# TempSensor.net
KiCad netlist of a schematic drawn in Altium Designer
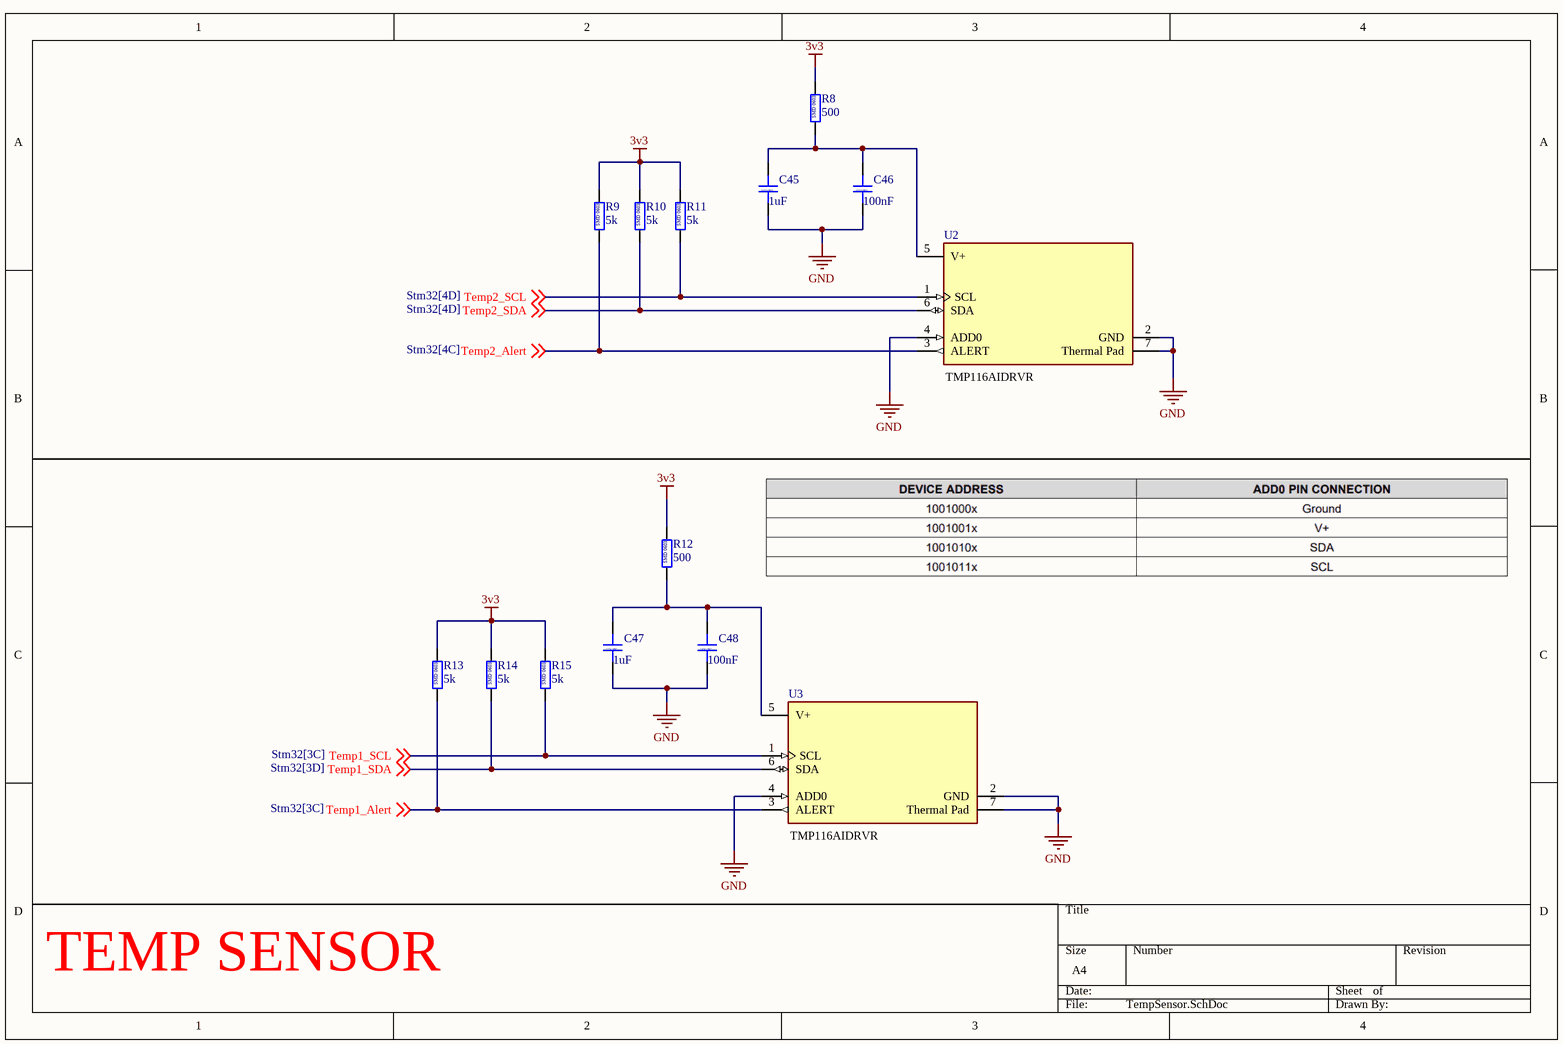
[diagram p0: TempSensor.SchDoc]

(export (version "E")
  (design (tool "Eeschema 10.0.6"))
  (components
    (comp (ref "C45")
      (value "1uF")
      (footprint "CAP_0603")
      (description "Capacitor SMD 0603 RATED")
      (libsource (lib "STeRG-Passives-Standard") (part "Capacitor-SMD-0603"))
    )
    (comp (ref "C46")
      (value "100nF")
      (footprint "CAP_0603")
      (description "Capacitor SMD 0603 RATED")
      (libsource (lib "STeRG-Passives-Standard") (part "Capacitor-SMD-0603"))
    )
    (comp (ref "C47")
      (value "1uF")
      (footprint "CAP_0603")
      (description "Capacitor SMD 0603 RATED")
      (libsource (lib "STeRG-Passives-Standard") (part "Capacitor-SMD-0603"))
    )
    (comp (ref "C48")
      (value "100nF")
      (footprint "CAP_0603")
      (description "Capacitor SMD 0603 RATED")
      (libsource (lib "STeRG-Passives-Standard") (part "Capacitor-SMD-0603"))
    )
    (comp (ref "R8")
      (value "500")
      (footprint "RES_0603")
      (description "Resistor SMD 0603 RATED")
      (libsource (lib "STeRG-Passives-Standard") (part "Resistor-SMD-0603"))
    )
    (comp (ref "R9")
      (value "5k")
      (footprint "RES_0603")
      (description "Resistor SMD 0603 RATED")
      (libsource (lib "STeRG-Passives-Standard") (part "Resistor-SMD-0603"))
    )
    (comp (ref "R10")
      (value "5k")
      (footprint "RES_0603")
      (description "Resistor SMD 0603 RATED")
      (libsource (lib "STeRG-Passives-Standard") (part "Resistor-SMD-0603"))
    )
    (comp (ref "R11")
      (value "5k")
      (footprint "RES_0603")
      (description "Resistor SMD 0603 RATED")
      (libsource (lib "STeRG-Passives-Standard") (part "Resistor-SMD-0603"))
    )
    (comp (ref "R12")
      (value "500")
      (footprint "RES_0603")
      (description "Resistor SMD 0603 RATED")
      (libsource (lib "STeRG-Passives-Standard") (part "Resistor-SMD-0603"))
    )
    (comp (ref "R13")
      (value "5k")
      (footprint "RES_0603")
      (description "Resistor SMD 0603 RATED")
      (libsource (lib "STeRG-Passives-Standard") (part "Resistor-SMD-0603"))
    )
    (comp (ref "R14")
      (value "5k")
      (footprint "RES_0603")
      (description "Resistor SMD 0603 RATED")
      (libsource (lib "STeRG-Passives-Standard") (part "Resistor-SMD-0603"))
    )
    (comp (ref "R15")
      (value "5k")
      (footprint "RES_0603")
      (description "Resistor SMD 0603 RATED")
      (libsource (lib "STeRG-Passives-Standard") (part "Resistor-SMD-0603"))
    )
    (comp (ref "U2")
      (value "~")
      (footprint "FP-DRV0006A-IPC_C")
      (description "SENSOR DIGITAL -55C-125C 6WSON")
      (libsource (lib "Altium Content Vault") (part "a617691ba8d4fd78c31dab07a1f4092"))
    )
    (comp (ref "U3")
      (value "~")
      (footprint "FP-DRV0006A-IPC_C")
      (description "SENSOR DIGITAL -55C-125C 6WSON")
      (libsource (lib "Altium Content Vault") (part "a617691ba8d4fd78c31dab07a1f4092"))
    )
  )
  (nets
    (net (code "1") (name "3v3") (class "Default")
      (node (ref "R10") (pin "2") (pinfunction "2_2") (pintype "passive"))
      (node (ref "R11") (pin "2") (pinfunction "2_2") (pintype "passive"))
      (node (ref "R12") (pin "2") (pinfunction "2_2") (pintype "passive"))
      (node (ref "R13") (pin "2") (pinfunction "2_2") (pintype "passive"))
      (node (ref "R14") (pin "2") (pinfunction "2_2") (pintype "passive"))
      (node (ref "R15") (pin "2") (pinfunction "2_2") (pintype "passive"))
      (node (ref "R8") (pin "2") (pinfunction "2_2") (pintype "passive"))
      (node (ref "R9") (pin "2") (pinfunction "2_2") (pintype "passive"))
    )
    (net (code "2") (name "GND") (class "Default")
      (node (ref "C45") (pin "1") (pinfunction "1_1") (pintype "passive"))
      (node (ref "C46") (pin "1") (pinfunction "1_1") (pintype "passive"))
      (node (ref "C47") (pin "1") (pinfunction "1_1") (pintype "passive"))
      (node (ref "C48") (pin "1") (pinfunction "1_1") (pintype "passive"))
      (node (ref "U2") (pin "2") (pinfunction "GND_2") (pintype "power_in"))
      (node (ref "U2") (pin "4") (pinfunction "ADD0_4") (pintype "input"))
      (node (ref "U2") (pin "7") (pinfunction "Thermal_Pad_7") (pintype "passive"))
      (node (ref "U3") (pin "2") (pinfunction "GND_2") (pintype "power_in"))
      (node (ref "U3") (pin "4") (pinfunction "ADD0_4") (pintype "input"))
      (node (ref "U3") (pin "7") (pinfunction "Thermal_Pad_7") (pintype "passive"))
    )
    (net (code "3") (name "Net-(U2-V+)") (class "Default")
      (node (ref "C45") (pin "2") (pinfunction "2_2") (pintype "passive"))
      (node (ref "C46") (pin "2") (pinfunction "2_2") (pintype "passive"))
      (node (ref "R8") (pin "1") (pinfunction "1_1") (pintype "passive"))
      (node (ref "U2") (pin "5") (pinfunction "V+_5") (pintype "power_in"))
    )
    (net (code "4") (name "Net-(U3-V+)") (class "Default")
      (node (ref "C47") (pin "2") (pinfunction "2_2") (pintype "passive"))
      (node (ref "C48") (pin "2") (pinfunction "2_2") (pintype "passive"))
      (node (ref "R12") (pin "1") (pinfunction "1_1") (pintype "passive"))
      (node (ref "U3") (pin "5") (pinfunction "V+_5") (pintype "power_in"))
    )
    (net (code "5") (name "Temp1_Alert") (class "Default")
      (node (ref "R13") (pin "1") (pinfunction "1_1") (pintype "passive"))
      (node (ref "U3") (pin "3") (pinfunction "ALERT_3") (pintype "output"))
    )
    (net (code "6") (name "Temp1_SCL") (class "Default")
      (node (ref "R15") (pin "1") (pinfunction "1_1") (pintype "passive"))
      (node (ref "U3") (pin "1") (pinfunction "SCL_1") (pintype "input"))
    )
    (net (code "7") (name "Temp1_SDA") (class "Default")
      (node (ref "R14") (pin "1") (pinfunction "1_1") (pintype "passive"))
      (node (ref "U3") (pin "6") (pinfunction "SDA_6") (pintype "bidirectional"))
    )
    (net (code "8") (name "Temp2_Alert") (class "Default")
      (node (ref "R9") (pin "1") (pinfunction "1_1") (pintype "passive"))
      (node (ref "U2") (pin "3") (pinfunction "ALERT_3") (pintype "output"))
    )
    (net (code "9") (name "Temp2_SCL") (class "Default")
      (node (ref "R11") (pin "1") (pinfunction "1_1") (pintype "passive"))
      (node (ref "U2") (pin "1") (pinfunction "SCL_1") (pintype "input"))
    )
    (net (code "10") (name "Temp2_SDA") (class "Default")
      (node (ref "R10") (pin "1") (pinfunction "1_1") (pintype "passive"))
      (node (ref "U2") (pin "6") (pinfunction "SDA_6") (pintype "bidirectional"))
    )
  )
)
